# F44.net
KiCad netlist of a schematic drawn in Altium Designer
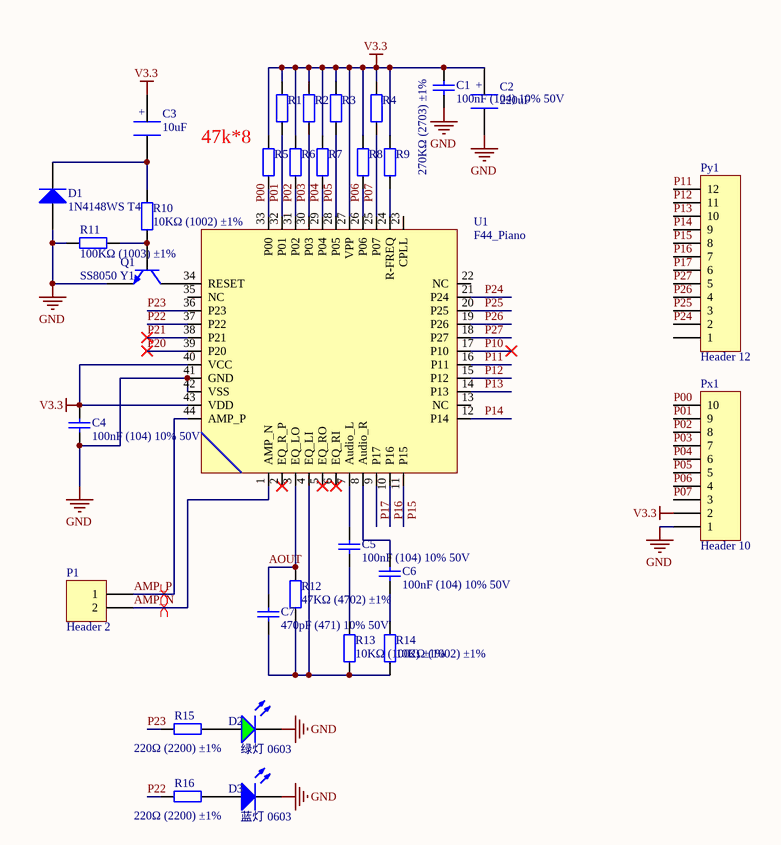
[diagram p0: F44.SchDoc]

(export (version "E")
  (design (tool "Eeschema 10.0.6"))
  (components
    (comp (ref "C1")
      (value "100nF (104) 10% 50V")
      (footprint "0603_C")
      (description "贴片电容")
      (libsource (lib "Miscellaneous Devices LC") (part "0603 100nF (104) 10% 50V"))
    )
    (comp (ref "C2") (value "220uF") (footprint "8X12_CAP") (libsource (lib "mylib") (part "CAP")))
    (comp (ref "C3") (value "10uF") (footprint "HDR1X2") (libsource (lib "mylib") (part "CAP")))
    (comp (ref "C4")
      (value "100nF (104) 10% 50V")
      (footprint "0603_C")
      (description "贴片电容")
      (libsource (lib "Miscellaneous Devices LC") (part "0603 100nF (104) 10% 50V"))
    )
    (comp (ref "C5")
      (value "100nF (104) 10% 50V")
      (footprint "0603_C")
      (description "贴片电容")
      (libsource (lib "Miscellaneous Devices LC") (part "0603 100nF (104) 10% 50V"))
    )
    (comp (ref "C6")
      (value "100nF (104) 10% 50V")
      (footprint "0603_C")
      (description "贴片电容")
      (libsource (lib "Miscellaneous Devices LC") (part "0603 100nF (104) 10% 50V"))
    )
    (comp (ref "C7")
      (value "470pF (471) 10% 50V")
      (footprint "0603_C")
      (description "贴片电容")
      (libsource (lib "Miscellaneous Devices LC") (part "0603 470pF (471) 10% 50V"))
    )
    (comp (ref "D1")
      (value "1N4148WS T4")
      (footprint "SOD-323")
      (description "二极管")
      (libsource (lib "Miscellaneous Devices LC") (part "SOD-323 1N4148WS T4"))
    )
    (comp (ref "D2")
      (value "绿灯 0603")
      (footprint "0603_LED_S1")
      (description "发光二极管")
      (libsource (lib "Miscellaneous Devices LC") (part "0603 绿灯"))
    )
    (comp (ref "D3")
      (value "蓝灯 0603")
      (footprint "0603_LED_S1")
      (description "发光二极管")
      (libsource (lib "Miscellaneous Devices LC") (part "0603 蓝灯"))
    )
    (comp (ref "P1")
      (value "Header 2")
      (footprint "XH2.54-WS-2P")
      (description "Header, 2-Pin")
      (fields (field (name "PUBLISHER") "Altium Limited"))
      (libsource (lib "Miscellaneous Connectors") (part "Header 2"))
    )
    (comp (ref "Px1")
      (value "Header 10")
      (footprint "FPC1.0-2H-WS-10P")
      (description "Header, 10-Pin")
      (fields (field (name "PUBLISHER") "Altium Limited"))
      (libsource (lib "Miscellaneous Connectors") (part "Header 10"))
    )
    (comp (ref "Py1")
      (value "Header 12")
      (footprint "FPC1.0-2H-WS-12P")
      (description "Header, 12-Pin")
      (fields (field (name "PUBLISHER") "Altium Limited"))
      (libsource (lib "Miscellaneous Connectors") (part "Header 12"))
    )
    (comp (ref "Q1")
      (value "SS8050 Y1")
      (footprint "SOT-23(SOT-23-3)")
      (description "三极管")
      (libsource (lib "Miscellaneous Devices LC") (part "SOT-23 SS8050 Y1"))
    )
    (comp (ref "R1")
      (value "47KΩ (4702) ±1%")
      (footprint "0603_R")
      (description "贴片电阻")
      (libsource (lib "Miscellaneous Devices LC") (part "0603 47KΩ (4702) 1%"))
    )
    (comp (ref "R2")
      (value "47KΩ (4702) ±1%")
      (footprint "0603_R")
      (description "贴片电阻")
      (libsource (lib "Miscellaneous Devices LC") (part "0603 47KΩ (4702) 1%"))
    )
    (comp (ref "R3")
      (value "47KΩ (4702) ±1%")
      (footprint "0603_R")
      (description "贴片电阻")
      (libsource (lib "Miscellaneous Devices LC") (part "0603 47KΩ (4702) 1%"))
    )
    (comp (ref "R4")
      (value "47KΩ (4702) ±1%")
      (footprint "0603_R")
      (description "贴片电阻")
      (libsource (lib "Miscellaneous Devices LC") (part "0603 47KΩ (4702) 1%"))
    )
    (comp (ref "R5")
      (value "47KΩ (4702) ±1%")
      (footprint "0603_R")
      (description "贴片电阻")
      (libsource (lib "Miscellaneous Devices LC") (part "0603 47KΩ (4702) 1%"))
    )
    (comp (ref "R6")
      (value "47KΩ (4702) ±1%")
      (footprint "0603_R")
      (description "贴片电阻")
      (libsource (lib "Miscellaneous Devices LC") (part "0603 47KΩ (4702) 1%"))
    )
    (comp (ref "R7")
      (value "47KΩ (4702) ±1%")
      (footprint "0603_R")
      (description "贴片电阻")
      (libsource (lib "Miscellaneous Devices LC") (part "0603 47KΩ (4702) 1%"))
    )
    (comp (ref "R8")
      (value "47KΩ (4702) ±1%")
      (footprint "0603_R")
      (description "贴片电阻")
      (libsource (lib "Miscellaneous Devices LC") (part "0603 47KΩ (4702) 1%"))
    )
    (comp (ref "R9")
      (value "270KΩ (2703) ±1%")
      (footprint "0603_R")
      (description "贴片电阻")
      (libsource (lib "Miscellaneous Devices LC") (part "0603 270KΩ (2703) 1%"))
    )
    (comp (ref "R10")
      (value "10KΩ (1002) ±1%")
      (footprint "0603_R")
      (description "贴片电阻")
      (libsource (lib "Miscellaneous Devices LC") (part "0603 10KΩ (1002) 1%"))
    )
    (comp (ref "R11")
      (value "100KΩ (1003) ±1%")
      (footprint "0603_R")
      (description "贴片电阻")
      (libsource (lib "Miscellaneous Devices LC") (part "0603 100KΩ (1003) 1%"))
    )
    (comp (ref "R12")
      (value "47KΩ (4702) ±1%")
      (footprint "0603_R")
      (description "贴片电阻")
      (libsource (lib "Miscellaneous Devices LC") (part "0603 47KΩ (4702) 1%"))
    )
    (comp (ref "R13")
      (value "10KΩ (1002) ±1%")
      (footprint "0603_R")
      (description "贴片电阻")
      (libsource (lib "Miscellaneous Devices LC") (part "0603 10KΩ (1002) 1%"))
    )
    (comp (ref "R14")
      (value "10KΩ (1002) ±1%")
      (footprint "0603_R")
      (description "贴片电阻")
      (libsource (lib "Miscellaneous Devices LC") (part "0603 10KΩ (1002) 1%"))
    )
    (comp (ref "R15")
      (value "220Ω (2200) ±1%")
      (footprint "0603_R")
      (description "贴片电阻")
      (libsource (lib "Miscellaneous Devices LC") (part "0603 220Ω (2200) 1%"))
    )
    (comp (ref "R16")
      (value "220Ω (2200) ±1%")
      (footprint "0603_R")
      (description "贴片电阻")
      (libsource (lib "Miscellaneous Devices LC") (part "0603 220Ω (2200) 1%"))
    )
    (comp (ref "U1")
      (value "F44_Piano")
      (footprint "LQFP-44_10x10x08P")
      (libsource (lib "mylib") (part "F44_Piano"))
    )
  )
  (nets
    (net (code "1") (name "/AMP_N") (class "Default")
      (node (ref "P1") (pin "2") (pinfunction "2_2") (pintype "passive"))
      (node (ref "U1") (pin "1") (pinfunction "AMP_N_1") (pintype "passive"))
    )
    (net (code "2") (name "/AMP_P") (class "Default")
      (node (ref "P1") (pin "1") (pinfunction "1_1") (pintype "passive"))
      (node (ref "U1") (pin "44") (pinfunction "AMP_P_44") (pintype "passive"))
    )
    (net (code "3") (name "/AOUT") (class "Default")
      (node (ref "C7") (pin "2") (pinfunction "2_2") (pintype "passive"))
      (node (ref "R12") (pin "2") (pinfunction "2_2") (pintype "passive"))
      (node (ref "U1") (pin "3") (pinfunction "EQ_LO_3") (pintype "passive"))
    )
    (net (code "4") (name "/P00") (class "Default")
      (node (ref "Px1") (pin "10") (pinfunction "10_10") (pintype "passive"))
      (node (ref "R5") (pin "1") (pinfunction "1_1") (pintype "passive"))
      (node (ref "U1") (pin "33") (pinfunction "P00_33") (pintype "passive"))
    )
    (net (code "5") (name "/P01") (class "Default")
      (node (ref "Px1") (pin "9") (pinfunction "9_9") (pintype "passive"))
      (node (ref "R1") (pin "1") (pinfunction "1_1") (pintype "passive"))
      (node (ref "U1") (pin "32") (pinfunction "P01_32") (pintype "passive"))
    )
    (net (code "6") (name "/P02") (class "Default")
      (node (ref "Px1") (pin "8") (pinfunction "8_8") (pintype "passive"))
      (node (ref "R6") (pin "1") (pinfunction "1_1") (pintype "passive"))
      (node (ref "U1") (pin "31") (pinfunction "P02_31") (pintype "passive"))
    )
    (net (code "7") (name "/P03") (class "Default")
      (node (ref "Px1") (pin "7") (pinfunction "7_7") (pintype "passive"))
      (node (ref "R2") (pin "1") (pinfunction "1_1") (pintype "passive"))
      (node (ref "U1") (pin "30") (pinfunction "P03_30") (pintype "passive"))
    )
    (net (code "8") (name "/P04") (class "Default")
      (node (ref "Px1") (pin "6") (pinfunction "6_6") (pintype "passive"))
      (node (ref "R7") (pin "1") (pinfunction "1_1") (pintype "passive"))
      (node (ref "U1") (pin "29") (pinfunction "P04_29") (pintype "passive"))
    )
    (net (code "9") (name "/P05") (class "Default")
      (node (ref "Px1") (pin "5") (pinfunction "5_5") (pintype "passive"))
      (node (ref "R3") (pin "1") (pinfunction "1_1") (pintype "passive"))
      (node (ref "U1") (pin "28") (pinfunction "P05_28") (pintype "passive"))
    )
    (net (code "10") (name "/P06") (class "Default")
      (node (ref "Px1") (pin "4") (pinfunction "4_4") (pintype "passive"))
      (node (ref "R8") (pin "1") (pinfunction "1_1") (pintype "passive"))
      (node (ref "U1") (pin "26") (pinfunction "P06_26") (pintype "passive"))
    )
    (net (code "11") (name "/P07") (class "Default")
      (node (ref "Px1") (pin "3") (pinfunction "3_3") (pintype "passive"))
      (node (ref "R4") (pin "1") (pinfunction "1_1") (pintype "passive"))
      (node (ref "U1") (pin "25") (pinfunction "P07_25") (pintype "passive"))
    )
    (net (code "12") (name "/P10") (class "Default")
      (node (ref "U1") (pin "17") (pinfunction "P10_17") (pintype "passive+no_connect"))
    )
    (net (code "13") (name "/P11") (class "Default")
      (node (ref "Py1") (pin "12") (pinfunction "12_12") (pintype "passive"))
      (node (ref "U1") (pin "16") (pinfunction "P11_16") (pintype "passive"))
    )
    (net (code "14") (name "/P12") (class "Default")
      (node (ref "Py1") (pin "11") (pinfunction "11_11") (pintype "passive"))
      (node (ref "U1") (pin "15") (pinfunction "P12_15") (pintype "passive"))
    )
    (net (code "15") (name "/P13") (class "Default")
      (node (ref "Py1") (pin "10") (pinfunction "10_10") (pintype "passive"))
      (node (ref "U1") (pin "14") (pinfunction "P13_14") (pintype "passive"))
    )
    (net (code "16") (name "/P14") (class "Default")
      (node (ref "Py1") (pin "9") (pinfunction "9_9") (pintype "passive"))
      (node (ref "U1") (pin "12") (pinfunction "P14_12") (pintype "passive"))
    )
    (net (code "17") (name "/P15") (class "Default")
      (node (ref "Py1") (pin "8") (pinfunction "8_8") (pintype "passive"))
      (node (ref "U1") (pin "11") (pinfunction "P15_11") (pintype "passive"))
    )
    (net (code "18") (name "/P16") (class "Default")
      (node (ref "Py1") (pin "7") (pinfunction "7_7") (pintype "passive"))
      (node (ref "U1") (pin "10") (pinfunction "P16_10") (pintype "passive"))
    )
    (net (code "19") (name "/P17") (class "Default")
      (node (ref "Py1") (pin "6") (pinfunction "6_6") (pintype "passive"))
      (node (ref "U1") (pin "9") (pinfunction "P17_9") (pintype "passive"))
    )
    (net (code "20") (name "/P20") (class "Default")
      (node (ref "U1") (pin "39") (pinfunction "P20_39") (pintype "passive+no_connect"))
    )
    (net (code "21") (name "/P21") (class "Default")
      (node (ref "U1") (pin "38") (pinfunction "P21_38") (pintype "passive+no_connect"))
    )
    (net (code "22") (name "/P22") (class "Default")
      (node (ref "R16") (pin "1") (pinfunction "1_1") (pintype "passive"))
      (node (ref "U1") (pin "37") (pinfunction "P22_37") (pintype "passive"))
    )
    (net (code "23") (name "/P23") (class "Default")
      (node (ref "R15") (pin "1") (pinfunction "1_1") (pintype "passive"))
      (node (ref "U1") (pin "36") (pinfunction "P23_36") (pintype "passive"))
    )
    (net (code "24") (name "/P24") (class "Default")
      (node (ref "Py1") (pin "2") (pinfunction "2_2") (pintype "passive"))
      (node (ref "U1") (pin "21") (pinfunction "P24_21") (pintype "passive"))
    )
    (net (code "25") (name "/P25") (class "Default")
      (node (ref "Py1") (pin "3") (pinfunction "3_3") (pintype "passive"))
      (node (ref "U1") (pin "20") (pinfunction "P25_20") (pintype "passive"))
    )
    (net (code "26") (name "/P26") (class "Default")
      (node (ref "Py1") (pin "4") (pinfunction "4_4") (pintype "passive"))
      (node (ref "U1") (pin "19") (pinfunction "P26_19") (pintype "passive"))
    )
    (net (code "27") (name "/P27") (class "Default")
      (node (ref "Py1") (pin "5") (pinfunction "5_5") (pintype "passive"))
      (node (ref "U1") (pin "18") (pinfunction "P27_18") (pintype "passive"))
    )
    (net (code "28") (name "GND") (class "Default")
      (node (ref "C1") (pin "1") (pinfunction "1_1") (pintype "passive"))
      (node (ref "C2") (pin "2") (pinfunction "2_2") (pintype "passive"))
      (node (ref "C4") (pin "2") (pinfunction "2_2") (pintype "passive"))
      (node (ref "D1") (pin "1") (pinfunction "A_1") (pintype "passive"))
      (node (ref "D2") (pin "K") (pinfunction "K_K") (pintype "passive"))
      (node (ref "D3") (pin "K") (pinfunction "K_K") (pintype "passive"))
      (node (ref "Px1") (pin "1") (pinfunction "1_1") (pintype "passive"))
      (node (ref "Q1") (pin "2") (pinfunction "E_2") (pintype "passive"))
      (node (ref "R11") (pin "1") (pinfunction "1_1") (pintype "passive"))
      (node (ref "U1") (pin "41") (pinfunction "GND_41") (pintype "passive"))
      (node (ref "U1") (pin "42") (pinfunction "VSS_42") (pintype "passive"))
    )
    (net (code "29") (name "Net-(C5-Pad1)") (class "Default")
      (node (ref "C5") (pin "1") (pinfunction "1_1") (pintype "passive"))
      (node (ref "R13") (pin "2") (pinfunction "2_2") (pintype "passive"))
    )
    (net (code "30") (name "Net-(C6-Pad1)") (class "Default")
      (node (ref "C6") (pin "1") (pinfunction "1_1") (pintype "passive"))
      (node (ref "R14") (pin "2") (pinfunction "2_2") (pintype "passive"))
    )
    (net (code "31") (name "Net-(D1-K)") (class "Default")
      (node (ref "C3") (pin "2") (pinfunction "2_2") (pintype "passive"))
      (node (ref "D1") (pin "2") (pinfunction "K_2") (pintype "passive"))
      (node (ref "R10") (pin "2") (pinfunction "2_2") (pintype "passive"))
    )
    (net (code "32") (name "Net-(D2-PadA)") (class "Default")
      (node (ref "D2") (pin "A") (pinfunction "A_A") (pintype "passive"))
      (node (ref "R15") (pin "2") (pinfunction "2_2") (pintype "passive"))
    )
    (net (code "33") (name "Net-(D3-PadA)") (class "Default")
      (node (ref "D3") (pin "A") (pinfunction "A_A") (pintype "passive"))
      (node (ref "R16") (pin "2") (pinfunction "2_2") (pintype "passive"))
    )
    (net (code "34") (name "Net-(Q1-B)") (class "Default")
      (node (ref "Q1") (pin "1") (pinfunction "B_1") (pintype "passive"))
      (node (ref "R10") (pin "1") (pinfunction "1_1") (pintype "passive"))
      (node (ref "R11") (pin "2") (pinfunction "2_2") (pintype "passive"))
    )
    (net (code "35") (name "Net-(Q1-C)") (class "Default")
      (node (ref "Q1") (pin "3") (pinfunction "C_3") (pintype "passive"))
      (node (ref "U1") (pin "34") (pinfunction "RESET_34") (pintype "passive"))
    )
    (net (code "36") (name "Net-(U1-Audio_L)") (class "Default")
      (node (ref "C5") (pin "2") (pinfunction "2_2") (pintype "passive"))
      (node (ref "U1") (pin "7") (pinfunction "Audio_L_7") (pintype "passive"))
    )
    (net (code "37") (name "Net-(U1-Audio_R)") (class "Default")
      (node (ref "C6") (pin "2") (pinfunction "2_2") (pintype "passive"))
      (node (ref "U1") (pin "8") (pinfunction "Audio_R_8") (pintype "passive"))
    )
    (net (code "38") (name "Net-(U1-EQ_LI)") (class "Default")
      (node (ref "C7") (pin "1") (pinfunction "1_1") (pintype "passive"))
      (node (ref "R12") (pin "1") (pinfunction "1_1") (pintype "passive"))
      (node (ref "R13") (pin "1") (pinfunction "1_1") (pintype "passive"))
      (node (ref "R14") (pin "1") (pinfunction "1_1") (pintype "passive"))
      (node (ref "U1") (pin "4") (pinfunction "EQ_LI_4") (pintype "passive"))
    )
    (net (code "39") (name "Net-(U1-R-FREQ)") (class "Default")
      (node (ref "R9") (pin "1") (pinfunction "1_1") (pintype "passive"))
      (node (ref "U1") (pin "24") (pinfunction "R-FREQ_24") (pintype "passive"))
    )
    (net (code "40") (name "V3.3") (class "Default")
      (node (ref "C1") (pin "2") (pinfunction "2_2") (pintype "passive"))
      (node (ref "C2") (pin "1") (pinfunction "1_1") (pintype "passive"))
      (node (ref "C3") (pin "1") (pinfunction "1_1") (pintype "passive"))
      (node (ref "C4") (pin "1") (pinfunction "1_1") (pintype "passive"))
      (node (ref "Px1") (pin "2") (pinfunction "2_2") (pintype "passive"))
      (node (ref "R1") (pin "2") (pinfunction "2_2") (pintype "passive"))
      (node (ref "R2") (pin "2") (pinfunction "2_2") (pintype "passive"))
      (node (ref "R3") (pin "2") (pinfunction "2_2") (pintype "passive"))
      (node (ref "R4") (pin "2") (pinfunction "2_2") (pintype "passive"))
      (node (ref "R5") (pin "2") (pinfunction "2_2") (pintype "passive"))
      (node (ref "R6") (pin "2") (pinfunction "2_2") (pintype "passive"))
      (node (ref "R7") (pin "2") (pinfunction "2_2") (pintype "passive"))
      (node (ref "R8") (pin "2") (pinfunction "2_2") (pintype "passive"))
      (node (ref "R9") (pin "2") (pinfunction "2_2") (pintype "passive"))
      (node (ref "U1") (pin "27") (pinfunction "VPP_27") (pintype "passive"))
      (node (ref "U1") (pin "40") (pinfunction "VCC_40") (pintype "passive"))
      (node (ref "U1") (pin "43") (pinfunction "VDD_43") (pintype "passive"))
    )
    (net (code "41") (name "unconnected-(Py1-Pad1)") (class "Default")
      (node (ref "Py1") (pin "1") (pinfunction "1_1") (pintype "passive"))
    )
    (net (code "42") (name "unconnected-(U1-CPLL-Pad23)") (class "Default")
      (node (ref "U1") (pin "23") (pinfunction "CPLL_23") (pintype "passive"))
    )
    (net (code "43") (name "unconnected-(U1-EQ_RI-Pad6)") (class "Default")
      (node (ref "U1") (pin "6") (pinfunction "EQ_RI_6") (pintype "passive+no_connect"))
    )
    (net (code "44") (name "unconnected-(U1-EQ_RO-Pad5)") (class "Default")
      (node (ref "U1") (pin "5") (pinfunction "EQ_RO_5") (pintype "passive+no_connect"))
    )
    (net (code "45") (name "unconnected-(U1-EQ_R_P-Pad2)") (class "Default")
      (node (ref "U1") (pin "2") (pinfunction "EQ_R_P_2") (pintype "passive+no_connect"))
    )
    (net (code "46") (name "unconnected-(U1-NC-Pad13)") (class "Default")
      (node (ref "U1") (pin "13") (pinfunction "NC_13") (pintype "passive"))
    )
    (net (code "47") (name "unconnected-(U1-NC-Pad22)") (class "Default")
      (node (ref "U1") (pin "22") (pinfunction "NC_22") (pintype "passive"))
    )
    (net (code "48") (name "unconnected-(U1-NC-Pad35)") (class "Default")
      (node (ref "U1") (pin "35") (pinfunction "NC_35") (pintype "passive"))
    )
  )
)
